# CONN_SEQ.net
KiCad netlist of a schematic drawn in Altium Designer
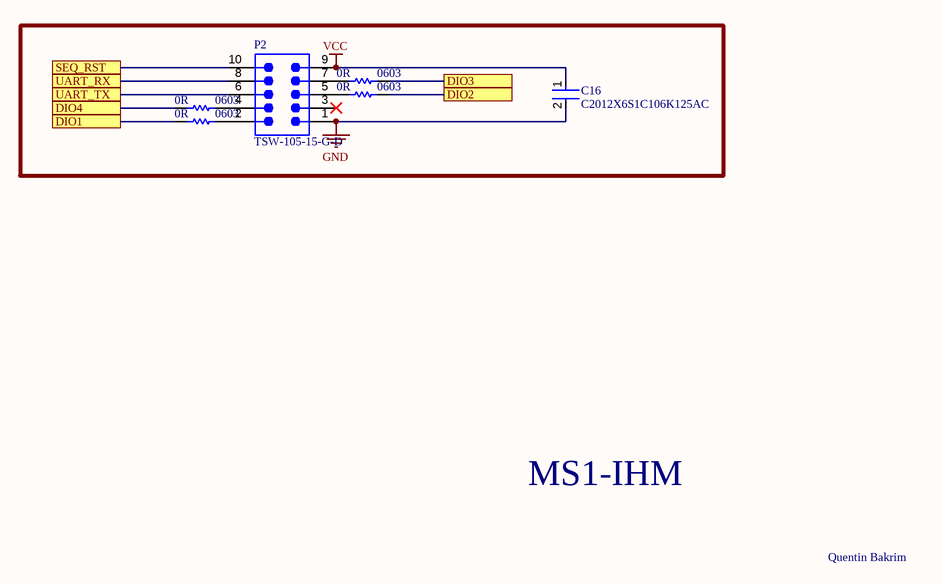
[diagram p0: CONN SEQ.SchDoc]

(export (version "E")
  (design (tool "Eeschema 10.0.6"))
  (components
    (comp (ref "C16")
      (value "C2012X6S1C106K125AC")
      (footprint "FP-C2012-125-0_2-MFG")
      (description "Multilayer Ceramic Capacitors 10μF ±10% 16V X6S SMD 0805")
      (fields (field (name "TOLERANCE") "10%"))
      (libsource (lib "Altium Content Vault") (part "b4654b650e69147ec39a6b967a45e02"))
    )
    (comp (ref "P2")
      (value "TSW-105-15-G-D")
      (footprint "SMTC-TSW-105-15-X-D")
      (description "0.025\" SQ Post Header, Through-hole, Vertical, -55 to 125 degC, 2.54 mm Pitch, 10-Pin, Male, RoHS")
      (fields (field (name "MANUFACTURER") "Samtec"))
      (libsource (lib "Altium Content Vault") (part "SMTC-TSW-105-X-X-D-X"))
    )
    (comp (ref "R46")
      (value "CRCW06030000Z0EA")
      (footprint "RESC1609X50X30NL8T20")
      (description "Chip Resistor, 0 Ohm, Jumper, 100 mW, -55 to 155 degC, 0603 (1608 Metric), RoHS, Tape and Reel")
      (fields
        (field (name "MANUFACTURER") "Vishay Semiconductor")
        (field (name "PACKAGEREFERENCE") "0603")
        (field (name "RESISTOR") "0R")
      )
      (libsource (lib "Altium Content Vault") (part "RES-2"))
    )
    (comp (ref "R47")
      (value "CRCW06030000Z0EA")
      (footprint "RESC1609X50X30NL8T20")
      (description "Chip Resistor, 0 Ohm, Jumper, 100 mW, -55 to 155 degC, 0603 (1608 Metric), RoHS, Tape and Reel")
      (fields
        (field (name "MANUFACTURER") "Vishay Semiconductor")
        (field (name "PACKAGEREFERENCE") "0603")
        (field (name "RESISTOR") "0R")
      )
      (libsource (lib "Altium Content Vault") (part "RES-2"))
    )
    (comp (ref "R48")
      (value "CRCW06030000Z0EA")
      (footprint "RESC1609X50X30NL8T20")
      (description "Chip Resistor, 0 Ohm, Jumper, 100 mW, -55 to 155 degC, 0603 (1608 Metric), RoHS, Tape and Reel")
      (fields
        (field (name "MANUFACTURER") "Vishay Semiconductor")
        (field (name "PACKAGEREFERENCE") "0603")
        (field (name "RESISTOR") "0R")
      )
      (libsource (lib "Altium Content Vault") (part "RES-2"))
    )
    (comp (ref "R49")
      (value "CRCW06030000Z0EA")
      (footprint "RESC1609X50X30NL8T20")
      (description "Chip Resistor, 0 Ohm, Jumper, 100 mW, -55 to 155 degC, 0603 (1608 Metric), RoHS, Tape and Reel")
      (fields
        (field (name "MANUFACTURER") "Vishay Semiconductor")
        (field (name "PACKAGEREFERENCE") "0603")
        (field (name "RESISTOR") "0R")
      )
      (libsource (lib "Altium Content Vault") (part "RES-2"))
    )
  )
  (nets
    (net (code "1") (name "/DIO1") (class "Default")
      (node (ref "R49") (pin "1") (pinfunction "1_1") (pintype "passive"))
    )
    (net (code "2") (name "/DIO2") (class "Default")
      (node (ref "R47") (pin "2") (pinfunction "2_2") (pintype "passive"))
    )
    (net (code "3") (name "/DIO3") (class "Default")
      (node (ref "R46") (pin "2") (pinfunction "2_2") (pintype "passive"))
    )
    (net (code "4") (name "/DIO4") (class "Default")
      (node (ref "R48") (pin "1") (pinfunction "1_1") (pintype "passive"))
    )
    (net (code "5") (name "/SEQ_RST") (class "Default")
      (node (ref "P2") (pin "10") (pinfunction "10_10") (pintype "passive"))
    )
    (net (code "6") (name "/UART_RX") (class "Default")
      (node (ref "P2") (pin "8") (pinfunction "8_8") (pintype "passive"))
    )
    (net (code "7") (name "/UART_TX") (class "Default")
      (node (ref "P2") (pin "6") (pinfunction "6_6") (pintype "passive"))
    )
    (net (code "8") (name "GND") (class "Default")
      (node (ref "C16") (pin "2") (pinfunction "2_2") (pintype "passive"))
      (node (ref "P2") (pin "1") (pinfunction "1_1") (pintype "passive"))
    )
    (net (code "9") (name "Net-(P2-Pad2)") (class "Default")
      (node (ref "P2") (pin "2") (pinfunction "2_2") (pintype "passive"))
      (node (ref "R49") (pin "2") (pinfunction "2_2") (pintype "passive"))
    )
    (net (code "10") (name "Net-(P2-Pad4)") (class "Default")
      (node (ref "P2") (pin "4") (pinfunction "4_4") (pintype "passive"))
      (node (ref "R48") (pin "2") (pinfunction "2_2") (pintype "passive"))
    )
    (net (code "11") (name "Net-(P2-Pad5)") (class "Default")
      (node (ref "P2") (pin "5") (pinfunction "5_5") (pintype "passive"))
      (node (ref "R47") (pin "1") (pinfunction "1_1") (pintype "passive"))
    )
    (net (code "12") (name "Net-(P2-Pad7)") (class "Default")
      (node (ref "P2") (pin "7") (pinfunction "7_7") (pintype "passive"))
      (node (ref "R46") (pin "1") (pinfunction "1_1") (pintype "passive"))
    )
    (net (code "13") (name "VCC") (class "Default")
      (node (ref "C16") (pin "1") (pinfunction "1_1") (pintype "passive"))
      (node (ref "P2") (pin "9") (pinfunction "9_9") (pintype "passive"))
    )
    (net (code "14") (name "unconnected-(P2-Pad3)") (class "Default")
      (node (ref "P2") (pin "3") (pinfunction "3_3") (pintype "passive+no_connect"))
    )
  )
)
